# ATMEGA2560_Board.net
KiCad netlist of a schematic drawn in EAGLE
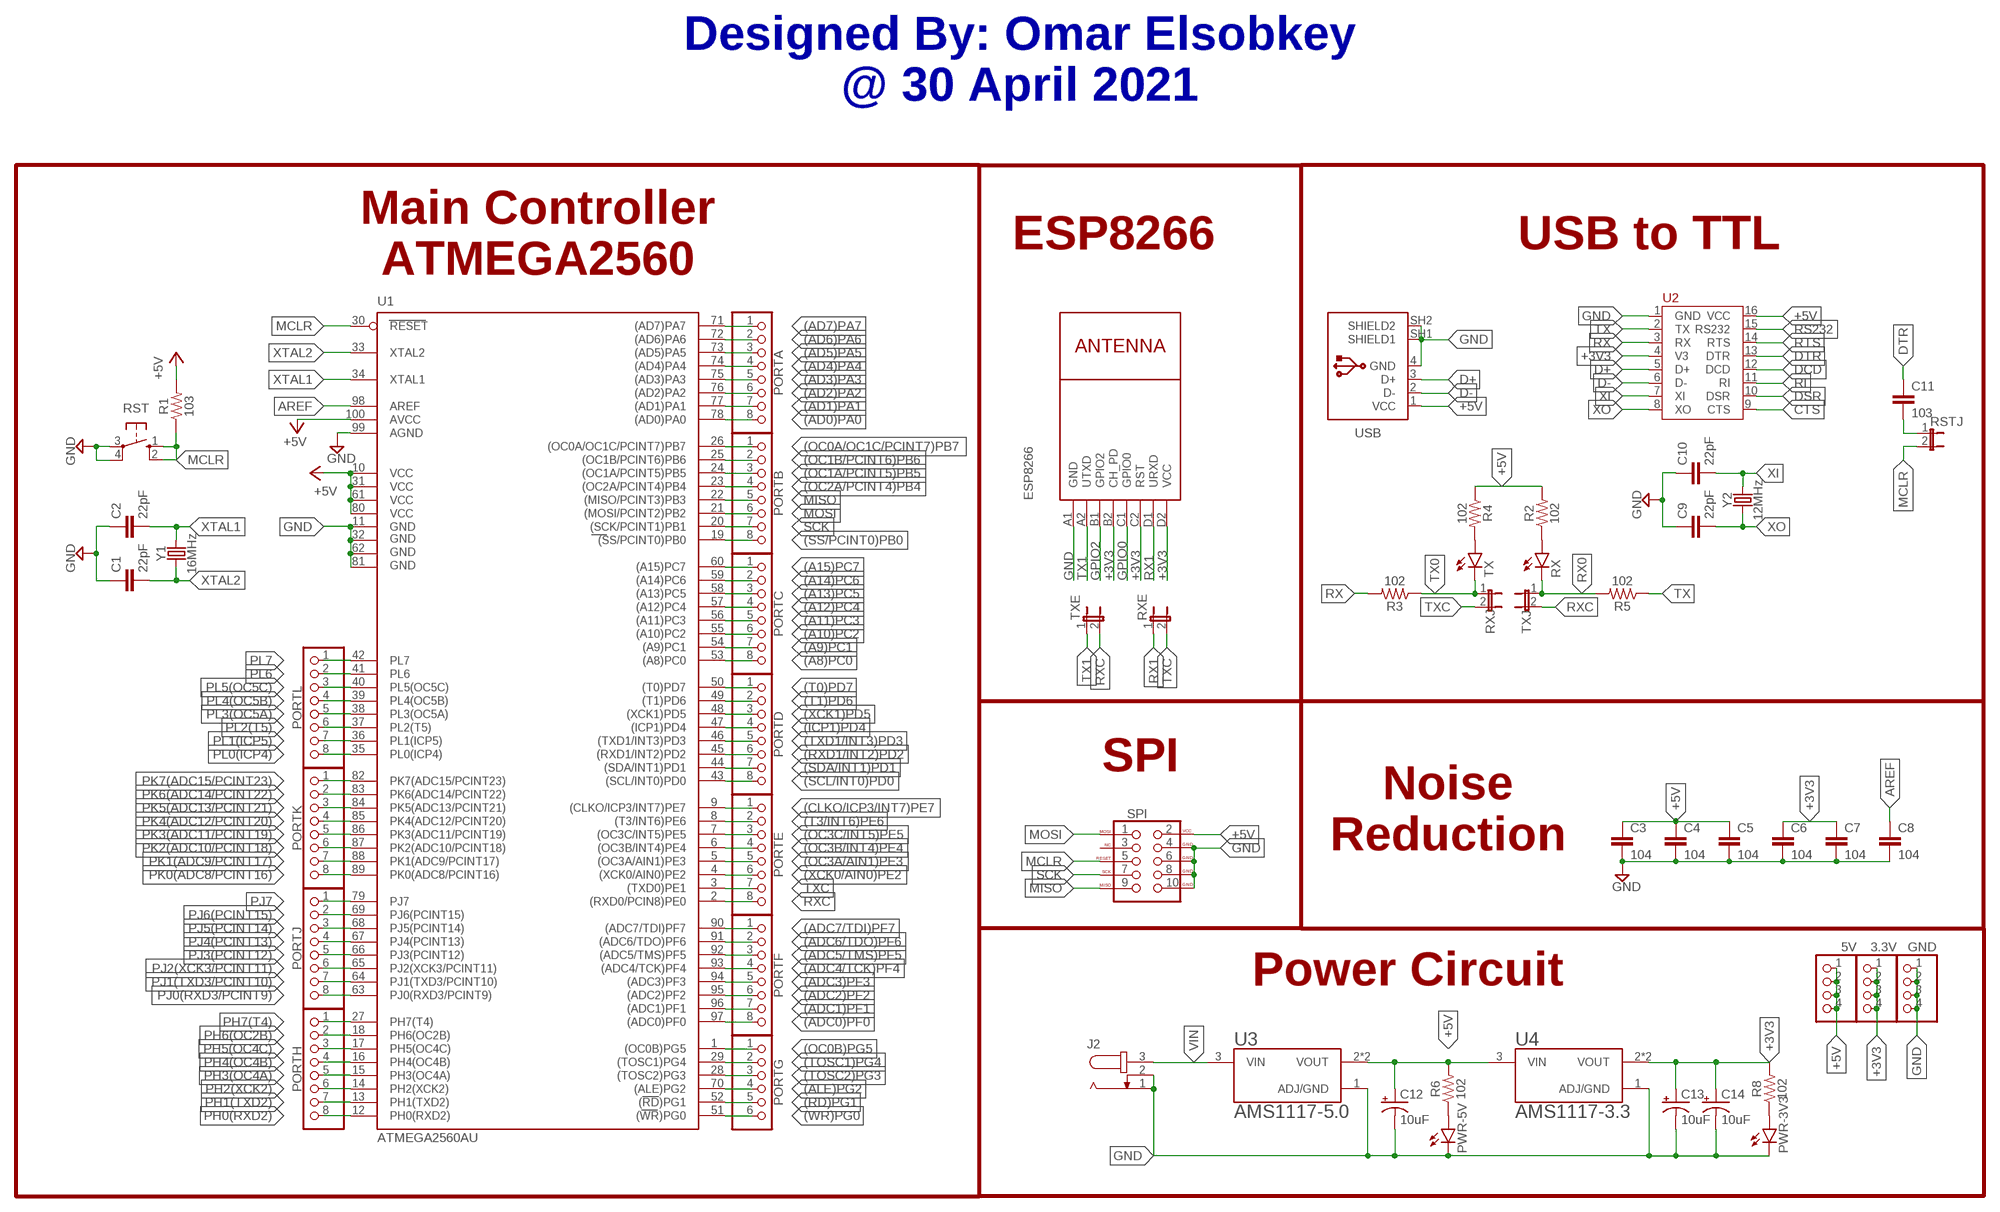
[diagram p0: schematic, sheet 1]

(export (version "E")
  (design (tool "Eeschema 10.0.6"))
  (components
    (comp (ref "3.3V")
      (value "PINHD-1X4")
      (footprint "eagle-import:1X04")
      (libsource (lib "eagle-import") (part "PINHD-1X4"))
    )
    (comp (ref "5V")
      (value "PINHD-1X4")
      (footprint "eagle-import:1X04")
      (libsource (lib "eagle-import") (part "PINHD-1X4"))
    )
    (comp (ref "C1")
      (value "22pF")
      (footprint "eagle-import:CAP-PTH-2.54")
      (libsource (lib "eagle-import") (part "22PF-PTH-2.54MM-200V-5%"))
    )
    (comp (ref "C2")
      (value "22pF")
      (footprint "eagle-import:CAP-PTH-2.54")
      (libsource (lib "eagle-import") (part "22PF-PTH-2.54MM-200V-5%"))
    )
    (comp (ref "C3")
      (value "104")
      (footprint "eagle-import:CAP-PTH-2.54")
      (libsource (lib "eagle-import") (part "22PF-PTH-2.54MM-200V-5%"))
    )
    (comp (ref "C4")
      (value "104")
      (footprint "eagle-import:CAP-PTH-2.54")
      (libsource (lib "eagle-import") (part "22PF-PTH-2.54MM-200V-5%"))
    )
    (comp (ref "C5")
      (value "104")
      (footprint "eagle-import:CAP-PTH-2.54")
      (libsource (lib "eagle-import") (part "22PF-PTH-2.54MM-200V-5%"))
    )
    (comp (ref "C6")
      (value "104")
      (footprint "eagle-import:CAP-PTH-2.54")
      (libsource (lib "eagle-import") (part "22PF-PTH-2.54MM-200V-5%"))
    )
    (comp (ref "C7")
      (value "104")
      (footprint "eagle-import:CAP-PTH-2.54")
      (libsource (lib "eagle-import") (part "22PF-PTH-2.54MM-200V-5%"))
    )
    (comp (ref "C8")
      (value "104")
      (footprint "eagle-import:CAP-PTH-2.54")
      (libsource (lib "eagle-import") (part "22PF-PTH-2.54MM-200V-5%"))
    )
    (comp (ref "C9")
      (value "22pF")
      (footprint "eagle-import:CAP-PTH-2.54")
      (libsource (lib "eagle-import") (part "22PF-PTH-2.54MM-200V-5%"))
    )
    (comp (ref "C10")
      (value "22pF")
      (footprint "eagle-import:CAP-PTH-2.54")
      (libsource (lib "eagle-import") (part "22PF-PTH-2.54MM-200V-5%"))
    )
    (comp (ref "C11")
      (value "103")
      (footprint "eagle-import:CAP-PTH-2.54")
      (libsource (lib "eagle-import") (part "22PF-PTH-2.54MM-200V-5%"))
    )
    (comp (ref "C12")
      (value "10uF")
      (footprint "eagle-import:CPOL-RADIAL-2.5MM-5MM-KIT")
      (libsource (lib "eagle-import") (part "10UF-POLAR-RADIAL-2.5MM-KIT-25V-20%"))
    )
    (comp (ref "C13")
      (value "10uF")
      (footprint "eagle-import:CPOL-RADIAL-2.5MM-5MM-KIT")
      (libsource (lib "eagle-import") (part "10UF-POLAR-RADIAL-2.5MM-KIT-25V-20%"))
    )
    (comp (ref "C14")
      (value "10uF")
      (footprint "eagle-import:CPOL-RADIAL-2.5MM-5MM-KIT")
      (libsource (lib "eagle-import") (part "10UF-POLAR-RADIAL-2.5MM-KIT-25V-20%"))
    )
    (comp (ref "ESP8266")
      (value "WIRELESS-WIFI-ESP-01")
      (footprint "eagle-import:WIRELESS-WIFI-ESP-01")
      (libsource (lib "eagle-import") (part "WIRELESS-WIFI-ESP-01"))
    )
    (comp (ref "GND")
      (value "PINHD-1X4")
      (footprint "eagle-import:1X04")
      (libsource (lib "eagle-import") (part "PINHD-1X4"))
    )
    (comp (ref "J2")
      (value "JACK-PLUG0")
      (footprint "eagle-import:SPC4077")
      (libsource (lib "eagle-import") (part "JACK-PLUG0"))
    )
    (comp (ref "PORTA")
      (value "PINHD-1X8")
      (footprint "eagle-import:1X08")
      (libsource (lib "eagle-import") (part "PINHD-1X8"))
    )
    (comp (ref "PORTB")
      (value "PINHD-1X8")
      (footprint "eagle-import:1X08")
      (libsource (lib "eagle-import") (part "PINHD-1X8"))
    )
    (comp (ref "PORTC")
      (value "PINHD-1X8")
      (footprint "eagle-import:1X08")
      (libsource (lib "eagle-import") (part "PINHD-1X8"))
    )
    (comp (ref "PORTD")
      (value "PINHD-1X8")
      (footprint "eagle-import:1X08")
      (libsource (lib "eagle-import") (part "PINHD-1X8"))
    )
    (comp (ref "PORTE")
      (value "PINHD-1X8")
      (footprint "eagle-import:1X08")
      (libsource (lib "eagle-import") (part "PINHD-1X8"))
    )
    (comp (ref "PORTF")
      (value "PINHD-1X8")
      (footprint "eagle-import:1X08")
      (libsource (lib "eagle-import") (part "PINHD-1X8"))
    )
    (comp (ref "PORTG")
      (value "PINHD-1X6")
      (footprint "eagle-import:1X06")
      (libsource (lib "eagle-import") (part "PINHD-1X6"))
    )
    (comp (ref "PORTH")
      (value "PINHD-1X8")
      (footprint "eagle-import:1X08")
      (libsource (lib "eagle-import") (part "PINHD-1X8"))
    )
    (comp (ref "PORTJ")
      (value "PINHD-1X8")
      (footprint "eagle-import:1X08")
      (libsource (lib "eagle-import") (part "PINHD-1X8"))
    )
    (comp (ref "PORTK")
      (value "PINHD-1X8")
      (footprint "eagle-import:1X08")
      (libsource (lib "eagle-import") (part "PINHD-1X8"))
    )
    (comp (ref "PORTL")
      (value "PINHD-1X8")
      (footprint "eagle-import:1X08")
      (libsource (lib "eagle-import") (part "PINHD-1X8"))
    )
    (comp (ref "PWR-3V3")
      (value "LEDCHIP-LED0805")
      (footprint "eagle-import:CHIP-LED0805")
      (libsource (lib "eagle-import") (part "LEDCHIP-LED0805"))
    )
    (comp (ref "PWR-5V")
      (value "LEDCHIP-LED0805")
      (footprint "eagle-import:CHIP-LED0805")
      (libsource (lib "eagle-import") (part "LEDCHIP-LED0805"))
    )
    (comp (ref "R1")
      (value "103")
      (footprint "eagle-import:1206")
      (libsource (lib "eagle-import") (part "RESISTOR1206"))
    )
    (comp (ref "R2")
      (value "102")
      (footprint "eagle-import:1206")
      (libsource (lib "eagle-import") (part "RESISTOR1206"))
    )
    (comp (ref "R3")
      (value "102")
      (footprint "eagle-import:1206")
      (libsource (lib "eagle-import") (part "RESISTOR1206"))
    )
    (comp (ref "R4")
      (value "102")
      (footprint "eagle-import:1206")
      (libsource (lib "eagle-import") (part "RESISTOR1206"))
    )
    (comp (ref "R5")
      (value "102")
      (footprint "eagle-import:1206")
      (libsource (lib "eagle-import") (part "RESISTOR1206"))
    )
    (comp (ref "R6")
      (value "102")
      (footprint "eagle-import:1206")
      (libsource (lib "eagle-import") (part "RESISTOR1206"))
    )
    (comp (ref "R8")
      (value "102")
      (footprint "eagle-import:1206")
      (libsource (lib "eagle-import") (part "RESISTOR1206"))
    )
    (comp (ref "RST")
      (value "10-XX")
      (footprint "eagle-import:B3F-10XX")
      (fields (field (name "MPN") "B3F-1000"))
      (libsource (lib "eagle-import") (part "10-XX"))
    )
    (comp (ref "RSTJ")
      (value "JP1E")
      (footprint "eagle-import:JP1")
      (libsource (lib "eagle-import") (part "JP1E"))
    )
    (comp (ref "RX")
      (value "LEDCHIP-LED0805")
      (footprint "eagle-import:CHIP-LED0805")
      (libsource (lib "eagle-import") (part "LEDCHIP-LED0805"))
    )
    (comp (ref "RXE")
      (value "JP1E")
      (footprint "eagle-import:JP1")
      (libsource (lib "eagle-import") (part "JP1E"))
    )
    (comp (ref "RXJ")
      (value "JP1E")
      (footprint "eagle-import:JP1")
      (libsource (lib "eagle-import") (part "JP1E"))
    )
    (comp (ref "SPI")
      (value "AVR_SPI_PROG_5X2LOCK")
      (footprint "eagle-import:2X5-SHROUDED_LOCK")
      (libsource (lib "eagle-import") (part "AVR_SPI_PROG_5X2LOCK"))
    )
    (comp (ref "TX")
      (value "LEDCHIP-LED0805")
      (footprint "eagle-import:CHIP-LED0805")
      (libsource (lib "eagle-import") (part "LEDCHIP-LED0805"))
    )
    (comp (ref "TXE")
      (value "JP1E")
      (footprint "eagle-import:JP1")
      (libsource (lib "eagle-import") (part "JP1E"))
    )
    (comp (ref "TXJ")
      (value "JP1E")
      (footprint "eagle-import:JP1")
      (libsource (lib "eagle-import") (part "JP1E"))
    )
    (comp (ref "U1")
      (value "ATMEGA2560AU")
      (footprint "eagle-import:TQFP100")
      (libsource (lib "eagle-import") (part "ATMEGA2560AU"))
    )
    (comp (ref "U2")
      (value "CH340G")
      (footprint "eagle-import:SOP-16")
      (libsource (lib "eagle-import") (part "CH340G"))
    )
    (comp (ref "U3")
      (value "AMS1117-5.0")
      (footprint "eagle-import:AMS1117-5.0")
      (fields (field (name "MF") "Advanced Monolithic Systems"))
      (libsource (lib "eagle-import") (part "AMS1117-5.0"))
    )
    (comp (ref "U4")
      (value "AMS1117-3.3")
      (footprint "eagle-import:AMS1117-5.0")
      (fields (field (name "MF") "Advanced Monolithic Systems") (field (name "MP") "AMS1117-5.0"))
      (libsource (lib "eagle-import") (part "AMS1117-5.0"))
    )
    (comp (ref "USB")
      (value "61729-1011")
      (footprint "eagle-import:61729-1011BLF")
      (fields (field (name "MANUFACTURER") "Amphenol ICC (FCI)") (field (name "MPN") "61729-1011BLF"))
      (libsource (lib "eagle-import") (part "61729-1011"))
    )
    (comp (ref "Y1")
      (value "16MHz")
      (footprint "eagle-import:HC49U")
      (libsource (lib "eagle-import") (part "CRYSTALPTH-HC49UV"))
    )
    (comp (ref "Y2")
      (value "12MHz")
      (footprint "eagle-import:HC49U")
      (libsource (lib "eagle-import") (part "CRYSTALPTH-HC49UV"))
    )
  )
  (nets
    (net (code "1") (name "(A8)PC0") (class "Default")
      (node (ref "PORTC") (pin "8") (pinfunction "8_8") (pintype "passive"))
      (node (ref "U1") (pin "53") (pinfunction "(A8)PC0_53") (pintype "bidirectional"))
    )
    (net (code "2") (name "(A9)PC1") (class "Default")
      (node (ref "PORTC") (pin "7") (pinfunction "7_7") (pintype "passive"))
      (node (ref "U1") (pin "54") (pinfunction "(A9)PC1_54") (pintype "bidirectional"))
    )
    (net (code "3") (name "(A10)PC2") (class "Default")
      (node (ref "PORTC") (pin "6") (pinfunction "6_6") (pintype "passive"))
      (node (ref "U1") (pin "55") (pinfunction "(A10)PC2_55") (pintype "bidirectional"))
    )
    (net (code "4") (name "(A11)PC3") (class "Default")
      (node (ref "PORTC") (pin "5") (pinfunction "5_5") (pintype "passive"))
      (node (ref "U1") (pin "56") (pinfunction "(A11)PC3_56") (pintype "bidirectional"))
    )
    (net (code "5") (name "(A12)PC4") (class "Default")
      (node (ref "PORTC") (pin "4") (pinfunction "4_4") (pintype "passive"))
      (node (ref "U1") (pin "57") (pinfunction "(A12)PC4_57") (pintype "bidirectional"))
    )
    (net (code "6") (name "(A13)PC5") (class "Default")
      (node (ref "PORTC") (pin "3") (pinfunction "3_3") (pintype "passive"))
      (node (ref "U1") (pin "58") (pinfunction "(A13)PC5_58") (pintype "bidirectional"))
    )
    (net (code "7") (name "(A14)PC6") (class "Default")
      (node (ref "PORTC") (pin "2") (pinfunction "2_2") (pintype "passive"))
      (node (ref "U1") (pin "59") (pinfunction "(A14)PC6_59") (pintype "bidirectional"))
    )
    (net (code "8") (name "(A15)PC7") (class "Default")
      (node (ref "PORTC") (pin "1") (pinfunction "1_1") (pintype "passive"))
      (node (ref "U1") (pin "60") (pinfunction "(A15)PC7_60") (pintype "bidirectional"))
    )
    (net (code "9") (name "(AD0)PA0") (class "Default")
      (node (ref "PORTA") (pin "8") (pinfunction "8_8") (pintype "passive"))
      (node (ref "U1") (pin "78") (pinfunction "(AD0)PA0_78") (pintype "bidirectional"))
    )
    (net (code "10") (name "(AD1)PA1") (class "Default")
      (node (ref "PORTA") (pin "7") (pinfunction "7_7") (pintype "passive"))
      (node (ref "U1") (pin "77") (pinfunction "(AD1)PA1_77") (pintype "bidirectional"))
    )
    (net (code "11") (name "(AD2)PA2") (class "Default")
      (node (ref "PORTA") (pin "6") (pinfunction "6_6") (pintype "passive"))
      (node (ref "U1") (pin "76") (pinfunction "(AD2)PA2_76") (pintype "bidirectional"))
    )
    (net (code "12") (name "(AD3)PA3") (class "Default")
      (node (ref "PORTA") (pin "5") (pinfunction "5_5") (pintype "passive"))
      (node (ref "U1") (pin "75") (pinfunction "(AD3)PA3_75") (pintype "bidirectional"))
    )
    (net (code "13") (name "(AD4)PA4") (class "Default")
      (node (ref "PORTA") (pin "4") (pinfunction "4_4") (pintype "passive"))
      (node (ref "U1") (pin "74") (pinfunction "(AD4)PA4_74") (pintype "bidirectional"))
    )
    (net (code "14") (name "(AD5)PA5") (class "Default")
      (node (ref "PORTA") (pin "3") (pinfunction "3_3") (pintype "passive"))
      (node (ref "U1") (pin "73") (pinfunction "(AD5)PA5_73") (pintype "bidirectional"))
    )
    (net (code "15") (name "(AD6)PA6") (class "Default")
      (node (ref "PORTA") (pin "2") (pinfunction "2_2") (pintype "passive"))
      (node (ref "U1") (pin "72") (pinfunction "(AD6)PA6_72") (pintype "bidirectional"))
    )
    (net (code "16") (name "(AD7)PA7") (class "Default")
      (node (ref "PORTA") (pin "1") (pinfunction "1_1") (pintype "passive"))
      (node (ref "U1") (pin "71") (pinfunction "(AD7)PA7_71") (pintype "bidirectional"))
    )
    (net (code "17") (name "(ADC0)PF0") (class "Default")
      (node (ref "PORTF") (pin "8") (pinfunction "8_8") (pintype "passive"))
      (node (ref "U1") (pin "97") (pinfunction "(ADC0)PF0_97") (pintype "bidirectional"))
    )
    (net (code "18") (name "(ADC1)PF1") (class "Default")
      (node (ref "PORTF") (pin "7") (pinfunction "7_7") (pintype "passive"))
      (node (ref "U1") (pin "96") (pinfunction "(ADC1)PF1_96") (pintype "bidirectional"))
    )
    (net (code "19") (name "(ADC2)PF2") (class "Default")
      (node (ref "PORTF") (pin "6") (pinfunction "6_6") (pintype "passive"))
      (node (ref "U1") (pin "95") (pinfunction "(ADC2)PF2_95") (pintype "bidirectional"))
    )
    (net (code "20") (name "(ADC3)PF3") (class "Default")
      (node (ref "PORTF") (pin "5") (pinfunction "5_5") (pintype "passive"))
      (node (ref "U1") (pin "94") (pinfunction "(ADC3)PF3_94") (pintype "bidirectional"))
    )
    (net (code "21") (name "(ADC4{slash}TCK)PF4") (class "Default")
      (node (ref "PORTF") (pin "4") (pinfunction "4_4") (pintype "passive"))
      (node (ref "U1") (pin "93") (pinfunction "(ADC4/TCK)PF4_93") (pintype "bidirectional"))
    )
    (net (code "22") (name "(ADC5{slash}TMS)PF5") (class "Default")
      (node (ref "PORTF") (pin "3") (pinfunction "3_3") (pintype "passive"))
      (node (ref "U1") (pin "92") (pinfunction "(ADC5/TMS)PF5_92") (pintype "bidirectional"))
    )
    (net (code "23") (name "(ADC6{slash}TDO)PF6") (class "Default")
      (node (ref "PORTF") (pin "2") (pinfunction "2_2") (pintype "passive"))
      (node (ref "U1") (pin "91") (pinfunction "(ADC6/TDO)PF6_91") (pintype "bidirectional"))
    )
    (net (code "24") (name "(ADC7{slash}TDI)PF7") (class "Default")
      (node (ref "PORTF") (pin "1") (pinfunction "1_1") (pintype "passive"))
      (node (ref "U1") (pin "90") (pinfunction "(ADC7/TDI)PF7_90") (pintype "bidirectional"))
    )
    (net (code "25") (name "(ALE)PG2") (class "Default")
      (node (ref "PORTG") (pin "4") (pinfunction "4_4") (pintype "passive"))
      (node (ref "U1") (pin "70") (pinfunction "(ALE)PG2_70") (pintype "bidirectional"))
    )
    (net (code "26") (name "(CLKO{slash}ICP3{slash}INT7)PE7") (class "Default")
      (node (ref "PORTE") (pin "1") (pinfunction "1_1") (pintype "passive"))
      (node (ref "U1") (pin "9") (pinfunction "(CLKO/ICP3/INT7)PE7_9") (pintype "bidirectional"))
    )
    (net (code "27") (name "(ICP1)PD4") (class "Default")
      (node (ref "PORTD") (pin "4") (pinfunction "4_4") (pintype "passive"))
      (node (ref "U1") (pin "47") (pinfunction "(ICP1)PD4_47") (pintype "bidirectional"))
    )
    (net (code "28") (name "(OC0A{slash}OC1C{slash}PCINT7)PB7") (class "Default")
      (node (ref "PORTB") (pin "1") (pinfunction "1_1") (pintype "passive"))
      (node (ref "U1") (pin "26") (pinfunction "(OC0A/OC1C/PCINT7)PB7_26") (pintype "bidirectional"))
    )
    (net (code "29") (name "(OC0B)PG5") (class "Default")
      (node (ref "PORTG") (pin "1") (pinfunction "1_1") (pintype "passive"))
      (node (ref "U1") (pin "1") (pinfunction "(OC0B)PG5_1") (pintype "bidirectional"))
    )
    (net (code "30") (name "(OC1A{slash}PCINT5)PB5") (class "Default")
      (node (ref "PORTB") (pin "3") (pinfunction "3_3") (pintype "passive"))
      (node (ref "U1") (pin "24") (pinfunction "(OC1A/PCINT5)PB5_24") (pintype "bidirectional"))
    )
    (net (code "31") (name "(OC1B{slash}PCINT6)PB6") (class "Default")
      (node (ref "PORTB") (pin "2") (pinfunction "2_2") (pintype "passive"))
      (node (ref "U1") (pin "25") (pinfunction "(OC1B/PCINT6)PB6_25") (pintype "bidirectional"))
    )
    (net (code "32") (name "(OC2A{slash}PCINT4)PB4") (class "Default")
      (node (ref "PORTB") (pin "4") (pinfunction "4_4") (pintype "passive"))
      (node (ref "U1") (pin "23") (pinfunction "(OC2A/PCINT4)PB4_23") (pintype "bidirectional"))
    )
    (net (code "33") (name "(OC3A{slash}AIN1)PE3") (class "Default")
      (node (ref "PORTE") (pin "5") (pinfunction "5_5") (pintype "passive"))
      (node (ref "U1") (pin "5") (pinfunction "(OC3A/AIN1)PE3_5") (pintype "bidirectional"))
    )
    (net (code "34") (name "(OC3B{slash}INT4)PE4") (class "Default")
      (node (ref "PORTE") (pin "4") (pinfunction "4_4") (pintype "passive"))
      (node (ref "U1") (pin "6") (pinfunction "(OC3B/INT4)PE4_6") (pintype "bidirectional"))
    )
    (net (code "35") (name "(OC3C{slash}INT5)PE5") (class "Default")
      (node (ref "PORTE") (pin "3") (pinfunction "3_3") (pintype "passive"))
      (node (ref "U1") (pin "7") (pinfunction "(OC3C/INT5)PE5_7") (pintype "bidirectional"))
    )
    (net (code "36") (name "(RD)PG1") (class "Default")
      (node (ref "PORTG") (pin "5") (pinfunction "5_5") (pintype "passive"))
      (node (ref "U1") (pin "52") (pinfunction "(RD)PG1_52") (pintype "bidirectional"))
    )
    (net (code "37") (name "(RXD1{slash}INT2)PD2") (class "Default")
      (node (ref "PORTD") (pin "6") (pinfunction "6_6") (pintype "passive"))
      (node (ref "U1") (pin "45") (pinfunction "(RXD1/INT2)PD2_45") (pintype "bidirectional"))
    )
    (net (code "38") (name "(SCL{slash}INT0)PD0") (class "Default")
      (node (ref "PORTD") (pin "8") (pinfunction "8_8") (pintype "passive"))
      (node (ref "U1") (pin "43") (pinfunction "(SCL/INT0)PD0_43") (pintype "bidirectional"))
    )
    (net (code "39") (name "(SDA{slash}INT1)PD1") (class "Default")
      (node (ref "PORTD") (pin "7") (pinfunction "7_7") (pintype "passive"))
      (node (ref "U1") (pin "44") (pinfunction "(SDA/INT1)PD1_44") (pintype "bidirectional"))
    )
    (net (code "40") (name "(SS{slash}PCINT0)PB0") (class "Default")
      (node (ref "PORTB") (pin "8") (pinfunction "8_8") (pintype "passive"))
      (node (ref "U1") (pin "19") (pinfunction "(SS/PCINT0)PB0_19") (pintype "bidirectional"))
    )
    (net (code "41") (name "(T0)PD7") (class "Default")
      (node (ref "PORTD") (pin "1") (pinfunction "1_1") (pintype "passive"))
      (node (ref "U1") (pin "50") (pinfunction "(T0)PD7_50") (pintype "bidirectional"))
    )
    (net (code "42") (name "(T1)PD6") (class "Default")
      (node (ref "PORTD") (pin "2") (pinfunction "2_2") (pintype "passive"))
      (node (ref "U1") (pin "49") (pinfunction "(T1)PD6_49") (pintype "bidirectional"))
    )
    (net (code "43") (name "(T3{slash}INT6)PE6") (class "Default")
      (node (ref "PORTE") (pin "2") (pinfunction "2_2") (pintype "passive"))
      (node (ref "U1") (pin "8") (pinfunction "(T3/INT6)PE6_8") (pintype "bidirectional"))
    )
    (net (code "44") (name "(TOSC1)PG4") (class "Default")
      (node (ref "PORTG") (pin "2") (pinfunction "2_2") (pintype "passive"))
      (node (ref "U1") (pin "29") (pinfunction "(TOSC1)PG4_29") (pintype "bidirectional"))
    )
    (net (code "45") (name "(TOSC2)PG3") (class "Default")
      (node (ref "PORTG") (pin "3") (pinfunction "3_3") (pintype "passive"))
      (node (ref "U1") (pin "28") (pinfunction "(TOSC2)PG3_28") (pintype "bidirectional"))
    )
    (net (code "46") (name "(TXD1{slash}INT3)PD3") (class "Default")
      (node (ref "PORTD") (pin "5") (pinfunction "5_5") (pintype "passive"))
      (node (ref "U1") (pin "46") (pinfunction "(TXD1/INT3)PD3_46") (pintype "bidirectional"))
    )
    (net (code "47") (name "(WR)PG0") (class "Default")
      (node (ref "PORTG") (pin "6") (pinfunction "6_6") (pintype "passive"))
      (node (ref "U1") (pin "51") (pinfunction "(WR)PG0_51") (pintype "bidirectional"))
    )
    (net (code "48") (name "(XCK0{slash}AIN0)PE2") (class "Default")
      (node (ref "PORTE") (pin "6") (pinfunction "6_6") (pintype "passive"))
      (node (ref "U1") (pin "4") (pinfunction "(XCK0/AIN0)PE2_4") (pintype "bidirectional"))
    )
    (net (code "49") (name "(XCK1)PD5") (class "Default")
      (node (ref "PORTD") (pin "3") (pinfunction "3_3") (pintype "passive"))
      (node (ref "U1") (pin "48") (pinfunction "(XCK1)PD5_48") (pintype "bidirectional"))
    )
    (net (code "50") (name "+3V3") (class "Default")
      (node (ref "3.3V") (pin "1") (pinfunction "1_1") (pintype "passive"))
      (node (ref "3.3V") (pin "2") (pinfunction "2_2") (pintype "passive"))
      (node (ref "3.3V") (pin "3") (pinfunction "3_3") (pintype "passive"))
      (node (ref "3.3V") (pin "4") (pinfunction "4_4") (pintype "passive"))
      (node (ref "C13") (pin "1") (pinfunction "+_1") (pintype "passive"))
      (node (ref "C14") (pin "1") (pinfunction "+_1") (pintype "passive"))
      (node (ref "C6") (pin "1") (pinfunction "1_1") (pintype "passive"))
      (node (ref "C7") (pin "1") (pinfunction "1_1") (pintype "passive"))
      (node (ref "ESP8266") (pin "B2") (pinfunction "CH_PD_B2") (pintype "bidirectional"))
      (node (ref "ESP8266") (pin "C2") (pinfunction "RST_C2") (pintype "bidirectional"))
      (node (ref "ESP8266") (pin "D2") (pinfunction "VCC_D2") (pintype "power_in"))
      (node (ref "R8") (pin "2") (pinfunction "2_2") (pintype "passive"))
      (node (ref "U2") (pin "4") (pinfunction "V3_4") (pintype "bidirectional"))
      (node (ref "U4") (pin "2") (pinfunction "VOUT_2") (pintype "output"))
      (node (ref "U4") (pin "4") (pinfunction "VOUT_4") (pintype "output"))
    )
    (net (code "51") (name "+5V") (class "Default")
      (node (ref "5V") (pin "1") (pinfunction "1_1") (pintype "passive"))
      (node (ref "5V") (pin "2") (pinfunction "2_2") (pintype "passive"))
      (node (ref "5V") (pin "3") (pinfunction "3_3") (pintype "passive"))
      (node (ref "5V") (pin "4") (pinfunction "4_4") (pintype "passive"))
      (node (ref "C12") (pin "1") (pinfunction "+_1") (pintype "passive"))
      (node (ref "C3") (pin "1") (pinfunction "1_1") (pintype "passive"))
      (node (ref "C4") (pin "1") (pinfunction "1_1") (pintype "passive"))
      (node (ref "C5") (pin "1") (pinfunction "1_1") (pintype "passive"))
      (node (ref "R1") (pin "2") (pinfunction "2_2") (pintype "passive"))
      (node (ref "R2") (pin "2") (pinfunction "2_2") (pintype "passive"))
      (node (ref "R4") (pin "1") (pinfunction "1_1") (pintype "passive"))
      (node (ref "R6") (pin "2") (pinfunction "2_2") (pintype "passive"))
      (node (ref "SPI") (pin "2") (pinfunction "VCC_2") (pintype "power_in"))
      (node (ref "U1") (pin "10") (pinfunction "VCC_10") (pintype "power_in"))
      (node (ref "U1") (pin "100") (pinfunction "AVCC_100") (pintype "power_in"))
      (node (ref "U1") (pin "31") (pinfunction "VCC1_31") (pintype "power_in"))
      (node (ref "U1") (pin "61") (pinfunction "VCC2_61") (pintype "power_in"))
      (node (ref "U1") (pin "80") (pinfunction "VCC3_80") (pintype "power_in"))
      (node (ref "U2") (pin "16") (pinfunction "VCC_16") (pintype "bidirectional"))
      (node (ref "U3") (pin "2") (pinfunction "VOUT_2") (pintype "output"))
      (node (ref "U3") (pin "4") (pinfunction "VOUT_4") (pintype "output"))
      (node (ref "U4") (pin "3") (pinfunction "VIN_3") (pintype "input"))
      (node (ref "USB") (pin "1") (pinfunction "VCC_1") (pintype "power_in"))
    )
    (net (code "52") (name "/GPIO0") (class "Default")
      (node (ref "ESP8266") (pin "C1") (pinfunction "GPIO0_C1") (pintype "bidirectional"))
    )
    (net (code "53") (name "/GPIO2") (class "Default")
      (node (ref "ESP8266") (pin "B1") (pinfunction "GPIO2_B1") (pintype "bidirectional"))
    )
    (net (code "54") (name "AREF") (class "Default")
      (node (ref "C8") (pin "1") (pinfunction "1_1") (pintype "passive"))
      (node (ref "U1") (pin "98") (pinfunction "AREF_98") (pintype "bidirectional"))
    )
    (net (code "55") (name "CTS") (class "Default")
      (node (ref "U2") (pin "9") (pinfunction "CTS_9") (pintype "bidirectional"))
    )
    (net (code "56") (name "D+") (class "Default")
      (node (ref "U2") (pin "5") (pinfunction "D+_5") (pintype "bidirectional"))
      (node (ref "USB") (pin "3") (pinfunction "D+_3") (pintype "bidirectional"))
    )
    (net (code "57") (name "D-") (class "Default")
      (node (ref "U2") (pin "6") (pinfunction "D-_6") (pintype "bidirectional"))
      (node (ref "USB") (pin "2") (pinfunction "D-_2") (pintype "bidirectional"))
    )
    (net (code "58") (name "DCD") (class "Default")
      (node (ref "U2") (pin "12") (pinfunction "DCD_12") (pintype "bidirectional"))
    )
    (net (code "59") (name "DSR") (class "Default")
      (node (ref "U2") (pin "10") (pinfunction "DSR_10") (pintype "bidirectional"))
    )
    (net (code "60") (name "DTR") (class "Default")
      (node (ref "C11") (pin "1") (pinfunction "1_1") (pintype "passive"))
      (node (ref "U2") (pin "13") (pinfunction "DTR_13") (pintype "bidirectional"))
    )
    (net (code "61") (name "GND") (class "Default")
      (node (ref "C1") (pin "1") (pinfunction "1_1") (pintype "passive"))
      (node (ref "C10") (pin "1") (pinfunction "1_1") (pintype "passive"))
      (node (ref "C12") (pin "2") (pinfunction "-_2") (pintype "passive"))
      (node (ref "C13") (pin "2") (pinfunction "-_2") (pintype "passive"))
      (node (ref "C14") (pin "2") (pinfunction "-_2") (pintype "passive"))
      (node (ref "C2") (pin "1") (pinfunction "1_1") (pintype "passive"))
      (node (ref "C3") (pin "2") (pinfunction "2_2") (pintype "passive"))
      (node (ref "C4") (pin "2") (pinfunction "2_2") (pintype "passive"))
      (node (ref "C5") (pin "2") (pinfunction "2_2") (pintype "passive"))
      (node (ref "C6") (pin "2") (pinfunction "2_2") (pintype "passive"))
      (node (ref "C7") (pin "2") (pinfunction "2_2") (pintype "passive"))
      (node (ref "C8") (pin "2") (pinfunction "2_2") (pintype "passive"))
      (node (ref "C9") (pin "1") (pinfunction "1_1") (pintype "passive"))
      (node (ref "ESP8266") (pin "A1") (pinfunction "GND_A1") (pintype "power_in"))
      (node (ref "GND") (pin "1") (pinfunction "1_1") (pintype "passive"))
      (node (ref "GND") (pin "2") (pinfunction "2_2") (pintype "passive"))
      (node (ref "GND") (pin "3") (pinfunction "3_3") (pintype "passive"))
      (node (ref "GND") (pin "4") (pinfunction "4_4") (pintype "passive"))
      (node (ref "J2") (pin "1") (pinfunction "1_1") (pintype "passive"))
      (node (ref "J2") (pin "2") (pinfunction "2_2") (pintype "passive"))
      (node (ref "PWR-3V3") (pin "C") (pinfunction "C_C") (pintype "passive"))
      (node (ref "PWR-5V") (pin "C") (pinfunction "C_C") (pintype "passive"))
      (node (ref "RST") (pin "3") (pinfunction "P_3") (pintype "passive"))
      (node (ref "RST") (pin "4") (pinfunction "P1_4") (pintype "passive"))
      (node (ref "SPI") (pin "10") (pinfunction "GND_10") (pintype "power_in"))
      (node (ref "SPI") (pin "4") (pinfunction "GND_4") (pintype "power_in"))
      (node (ref "SPI") (pin "6") (pinfunction "GND_6") (pintype "power_in"))
      (node (ref "SPI") (pin "8") (pinfunction "GND_8") (pintype "power_in"))
      (node (ref "U1") (pin "11") (pinfunction "GND_11") (pintype "power_in"))
      (node (ref "U1") (pin "32") (pinfunction "GND1_32") (pintype "power_in"))
      (node (ref "U1") (pin "62") (pinfunction "GND2_62") (pintype "power_in"))
      (node (ref "U1") (pin "81") (pinfunction "GND3_81") (pintype "power_in"))
      (node (ref "U1") (pin "99") (pinfunction "AGND_99") (pintype "power_in"))
      (node (ref "U2") (pin "1") (pinfunction "GND_1") (pintype "bidirectional"))
      (node (ref "U3") (pin "1") (pinfunction "ADJ/GND_1") (pintype "power_in"))
      (node (ref "U4") (pin "1") (pinfunction "ADJ/GND_1") (pintype "power_in"))
      (node (ref "USB") (pin "4") (pinfunction "GND_4") (pintype "power_in"))
      (node (ref "USB") (pin "SH1") (pinfunction "SHIELD1_SH1") (pintype "power_in"))
      (node (ref "USB") (pin "SH2") (pinfunction "SHIELD2_SH2") (pintype "power_in"))
    )
    (net (code "62") (name "MCLR") (class "Default")
      (node (ref "R1") (pin "1") (pinfunction "1_1") (pintype "passive"))
      (node (ref "RST") (pin "1") (pinfunction "S_1") (pintype "passive"))
      (node (ref "RST") (pin "2") (pinfunction "S1_2") (pintype "passive"))
      (node (ref "RSTJ") (pin "2") (pinfunction "2_2") (pintype "passive"))
      (node (ref "SPI") (pin "5") (pinfunction "RESET_5") (pintype "passive"))
      (node (ref "U1") (pin "30") (pinfunction "RESET_30") (pintype "input"))
    )
    (net (code "63") (name "MISO") (class "Default")
      (node (ref "PORTB") (pin "5") (pinfunction "5_5") (pintype "passive"))
      (node (ref "SPI") (pin "9") (pinfunction "MISO_9") (pintype "passive"))
      (node (ref "U1") (pin "22") (pinfunction "(MISO/PCINT3)PB3_22") (pintype "bidirectional"))
    )
    (net (code "64") (name "MOSI") (class "Default")
      (node (ref "PORTB") (pin "6") (pinfunction "6_6") (pintype "passive"))
      (node (ref "SPI") (pin "1") (pinfunction "MOSI_1") (pintype "passive"))
      (node (ref "U1") (pin "21") (pinfunction "(MOSI/PCINT2)PB2_21") (pintype "bidirectional"))
    )
    (net (code "65") (name "Net-(C11-Pad2)") (class "Default")
      (node (ref "C11") (pin "2") (pinfunction "2_2") (pintype "passive"))
      (node (ref "RSTJ") (pin "1") (pinfunction "1_1") (pintype "passive"))
    )
    (net (code "66") (name "Net-(PWR-3V3-PadA)") (class "Default")
      (node (ref "PWR-3V3") (pin "A") (pinfunction "A_A") (pintype "passive"))
      (node (ref "R8") (pin "1") (pinfunction "1_1") (pintype "passive"))
    )
    (net (code "67") (name "Net-(PWR-5V-PadA)") (class "Default")
      (node (ref "PWR-5V") (pin "A") (pinfunction "A_A") (pintype "passive"))
      (node (ref "R6") (pin "1") (pinfunction "1_1") (pintype "passive"))
    )
    (net (code "68") (name "Net-(R2-Pad1)") (class "Default")
      (node (ref "R2") (pin "1") (pinfunction "1_1") (pintype "passive"))
      (node (ref "RX") (pin "A") (pinfunction "A_A") (pintype "passive"))
    )
    (net (code "69") (name "Net-(R4-Pad2)") (class "Default")
      (node (ref "R4") (pin "2") (pinfunction "2_2") (pintype "passive"))
      (node (ref "TX") (pin "A") (pinfunction "A_A") (pintype "passive"))
    )
    (net (code "70") (name "PH0(RXD2)") (class "Default")
      (node (ref "PORTH") (pin "8") (pinfunction "8_8") (pintype "passive"))
      (node (ref "U1") (pin "12") (pinfunction "PH0(RXD2)_12") (pintype "bidirectional"))
    )
    (net (code "71") (name "PH1(TXD2)") (class "Default")
      (node (ref "PORTH") (pin "7") (pinfunction "7_7") (pintype "passive"))
      (node (ref "U1") (pin "13") (pinfunction "PH1(TXD2)_13") (pintype "bidirectional"))
    )
    (net (code "72") (name "PH2(XCK2)") (class "Default")
      (node (ref "PORTH") (pin "6") (pinfunction "6_6") (pintype "passive"))
      (node (ref "U1") (pin "14") (pinfunction "PH2(XCK2)_14") (pintype "bidirectional"))
    )
    (net (code "73") (name "PH3(OC4A)") (class "Default")
      (node (ref "PORTH") (pin "5") (pinfunction "5_5") (pintype "passive"))
      (node (ref "U1") (pin "15") (pinfunction "PH3(OC4A)_15") (pintype "bidirectional"))
    )
    (net (code "74") (name "PH4(OC4B)") (class "Default")
      (node (ref "PORTH") (pin "4") (pinfunction "4_4") (pintype "passive"))
      (node (ref "U1") (pin "16") (pinfunction "PH4(OC4B)_16") (pintype "bidirectional"))
    )
    (net (code "75") (name "PH5(OC4C)") (class "Default")
      (node (ref "PORTH") (pin "3") (pinfunction "3_3") (pintype "passive"))
      (node (ref "U1") (pin "17") (pinfunction "PH5(OC4C)_17") (pintype "bidirectional"))
    )
    (net (code "76") (name "PH6(OC2B)") (class "Default")
      (node (ref "PORTH") (pin "2") (pinfunction "2_2") (pintype "passive"))
      (node (ref "U1") (pin "18") (pinfunction "PH6(OC2B)_18") (pintype "bidirectional"))
    )
    (net (code "77") (name "PH7(T4)") (class "Default")
      (node (ref "PORTH") (pin "1") (pinfunction "1_1") (pintype "passive"))
      (node (ref "U1") (pin "27") (pinfunction "PH7(T4)_27") (pintype "bidirectional"))
    )
    (net (code "78") (name "PJ0(RXD3{slash}PCINT9)") (class "Default")
      (node (ref "PORTJ") (pin "8") (pinfunction "8_8") (pintype "passive"))
      (node (ref "U1") (pin "63") (pinfunction "PJ0(RXD3/PCINT9)_63") (pintype "bidirectional"))
    )
    (net (code "79") (name "PJ1(TXD3{slash}PCINT10)") (class "Default")
      (node (ref "PORTJ") (pin "7") (pinfunction "7_7") (pintype "passive"))
      (node (ref "U1") (pin "64") (pinfunction "PJ1(TXD3/PCINT10)_64") (pintype "bidirectional"))
    )
    (net (code "80") (name "PJ2(XCK3{slash}PCINT11)") (class "Default")
      (node (ref "PORTJ") (pin "6") (pinfunction "6_6") (pintype "passive"))
      (node (ref "U1") (pin "65") (pinfunction "PJ2(XCK3/PCINT11)_65") (pintype "bidirectional"))
    )
    (net (code "81") (name "PJ3(PCINT12)") (class "Default")
      (node (ref "PORTJ") (pin "5") (pinfunction "5_5") (pintype "passive"))
      (node (ref "U1") (pin "66") (pinfunction "PJ3(PCINT12)_66") (pintype "bidirectional"))
    )
    (net (code "82") (name "PJ4(PCINT13)") (class "Default")
      (node (ref "PORTJ") (pin "4") (pinfunction "4_4") (pintype "passive"))
      (node (ref "U1") (pin "67") (pinfunction "PJ4(PCINT13)_67") (pintype "bidirectional"))
    )
    (net (code "83") (name "PJ5(PCINT14)") (class "Default")
      (node (ref "PORTJ") (pin "3") (pinfunction "3_3") (pintype "passive"))
      (node (ref "U1") (pin "68") (pinfunction "PJ5(PCINT14)_68") (pintype "bidirectional"))
    )
    (net (code "84") (name "PJ6(PCINT15)") (class "Default")
      (node (ref "PORTJ") (pin "2") (pinfunction "2_2") (pintype "passive"))
      (node (ref "U1") (pin "69") (pinfunction "PJ6(PCINT15)_69") (pintype "bidirectional"))
    )
    (net (code "85") (name "PJ7") (class "Default")
      (node (ref "PORTJ") (pin "1") (pinfunction "1_1") (pintype "passive"))
      (node (ref "U1") (pin "79") (pinfunction "PJ7_79") (pintype "bidirectional"))
    )
    (net (code "86") (name "PK0(ADC8{slash}PCINT16)") (class "Default")
      (node (ref "PORTK") (pin "8") (pinfunction "8_8") (pintype "passive"))
      (node (ref "U1") (pin "89") (pinfunction "PK0(ADC8/PCINT16)_89") (pintype "bidirectional"))
    )
    (net (code "87") (name "PK1(ADC9{slash}PCINT17)") (class "Default")
      (node (ref "PORTK") (pin "7") (pinfunction "7_7") (pintype "passive"))
      (node (ref "U1") (pin "88") (pinfunction "PK1(ADC9/PCINT17)_88") (pintype "bidirectional"))
    )
    (net (code "88") (name "PK2(ADC10{slash}PCINT18)") (class "Default")
      (node (ref "PORTK") (pin "6") (pinfunction "6_6") (pintype "passive"))
      (node (ref "U1") (pin "87") (pinfunction "PK2(ADC10/PCINT18)_87") (pintype "bidirectional"))
    )
    (net (code "89") (name "PK3(ADC11{slash}PCINT19)") (class "Default")
      (node (ref "PORTK") (pin "5") (pinfunction "5_5") (pintype "passive"))
      (node (ref "U1") (pin "86") (pinfunction "PK3(ADC11/PCINT19)_86") (pintype "bidirectional"))
    )
    (net (code "90") (name "PK4(ADC12{slash}PCINT20)") (class "Default")
      (node (ref "PORTK") (pin "4") (pinfunction "4_4") (pintype "passive"))
      (node (ref "U1") (pin "85") (pinfunction "PK4(ADC12/PCINT20)_85") (pintype "bidirectional"))
    )
    (net (code "91") (name "PK5(ADC13{slash}PCINT21)") (class "Default")
      (node (ref "PORTK") (pin "3") (pinfunction "3_3") (pintype "passive"))
      (node (ref "U1") (pin "84") (pinfunction "PK5(ADC13/PCINT21)_84") (pintype "bidirectional"))
    )
    (net (code "92") (name "PK6(ADC14{slash}PCINT22)") (class "Default")
      (node (ref "PORTK") (pin "2") (pinfunction "2_2") (pintype "passive"))
      (node (ref "U1") (pin "83") (pinfunction "PK6(ADC14/PCINT22)_83") (pintype "bidirectional"))
    )
    (net (code "93") (name "PK7(ADC15{slash}PCINT23)") (class "Default")
      (node (ref "PORTK") (pin "1") (pinfunction "1_1") (pintype "passive"))
      (node (ref "U1") (pin "82") (pinfunction "PK7(ADC15/PCINT23)_82") (pintype "bidirectional"))
    )
    (net (code "94") (name "PL0(ICP4)") (class "Default")
      (node (ref "PORTL") (pin "8") (pinfunction "8_8") (pintype "passive"))
      (node (ref "U1") (pin "35") (pinfunction "PL0(ICP4)_35") (pintype "bidirectional"))
    )
    (net (code "95") (name "PL1(ICP5)") (class "Default")
      (node (ref "PORTL") (pin "7") (pinfunction "7_7") (pintype "passive"))
      (node (ref "U1") (pin "36") (pinfunction "PL1(ICP5)_36") (pintype "bidirectional"))
    )
    (net (code "96") (name "PL2(T5)") (class "Default")
      (node (ref "PORTL") (pin "6") (pinfunction "6_6") (pintype "passive"))
      (node (ref "U1") (pin "37") (pinfunction "PL2(T5)_37") (pintype "bidirectional"))
    )
    (net (code "97") (name "PL3(OC5A)") (class "Default")
      (node (ref "PORTL") (pin "5") (pinfunction "5_5") (pintype "passive"))
      (node (ref "U1") (pin "38") (pinfunction "PL3(OC5A)_38") (pintype "bidirectional"))
    )
    (net (code "98") (name "PL4(OC5B)") (class "Default")
      (node (ref "PORTL") (pin "4") (pinfunction "4_4") (pintype "passive"))
      (node (ref "U1") (pin "39") (pinfunction "PL4(OC5B)_39") (pintype "bidirectional"))
    )
    (net (code "99") (name "PL5(OC5C)") (class "Default")
      (node (ref "PORTL") (pin "3") (pinfunction "3_3") (pintype "passive"))
      (node (ref "U1") (pin "40") (pinfunction "PL5(OC5C)_40") (pintype "bidirectional"))
    )
    (net (code "100") (name "PL6") (class "Default")
      (node (ref "PORTL") (pin "2") (pinfunction "2_2") (pintype "passive"))
      (node (ref "U1") (pin "41") (pinfunction "PL6_41") (pintype "bidirectional"))
    )
    (net (code "101") (name "PL7") (class "Default")
      (node (ref "PORTL") (pin "1") (pinfunction "1_1") (pintype "passive"))
      (node (ref "U1") (pin "42") (pinfunction "PL7_42") (pintype "bidirectional"))
    )
    (net (code "102") (name "RI") (class "Default")
      (node (ref "U2") (pin "11") (pinfunction "RI_11") (pintype "bidirectional"))
    )
    (net (code "103") (name "RS232") (class "Default")
      (node (ref "U2") (pin "15") (pinfunction "RS232_15") (pintype "bidirectional"))
    )
    (net (code "104") (name "RTS") (class "Default")
      (node (ref "U2") (pin "14") (pinfunction "RTS_14") (pintype "bidirectional"))
    )
    (net (code "105") (name "RX") (class "Default")
      (node (ref "R3") (pin "2") (pinfunction "2_2") (pintype "passive"))
      (node (ref "U2") (pin "3") (pinfunction "RX_3") (pintype "bidirectional"))
    )
    (net (code "106") (name "RX0") (class "Default")
      (node (ref "R5") (pin "2") (pinfunction "2_2") (pintype "passive"))
      (node (ref "RX") (pin "C") (pinfunction "C_C") (pintype "passive"))
      (node (ref "TXJ") (pin "1") (pinfunction "1_1") (pintype "passive"))
    )
    (net (code "107") (name "RX1") (class "Default")
      (node (ref "ESP8266") (pin "D1") (pinfunction "URXD_D1") (pintype "bidirectional"))
      (node (ref "RXE") (pin "1") (pinfunction "1_1") (pintype "passive"))
    )
    (net (code "108") (name "RXC") (class "Default")
      (node (ref "PORTE") (pin "8") (pinfunction "8_8") (pintype "passive"))
      (node (ref "TXE") (pin "2") (pinfunction "2_2") (pintype "passive"))
      (node (ref "TXJ") (pin "2") (pinfunction "2_2") (pintype "passive"))
      (node (ref "U1") (pin "2") (pinfunction "(RXD0/PCIN8)PE0_2") (pintype "bidirectional"))
    )
    (net (code "109") (name "SCK") (class "Default")
      (node (ref "PORTB") (pin "7") (pinfunction "7_7") (pintype "passive"))
      (node (ref "SPI") (pin "7") (pinfunction "SCK_7") (pintype "passive"))
      (node (ref "U1") (pin "20") (pinfunction "(SCK/PCINT1)PB1_20") (pintype "bidirectional"))
    )
    (net (code "110") (name "TX") (class "Default")
      (node (ref "R5") (pin "1") (pinfunction "1_1") (pintype "passive"))
      (node (ref "U2") (pin "2") (pinfunction "TX_2") (pintype "bidirectional"))
    )
    (net (code "111") (name "TX0") (class "Default")
      (node (ref "R3") (pin "1") (pinfunction "1_1") (pintype "passive"))
      (node (ref "RXJ") (pin "1") (pinfunction "1_1") (pintype "passive"))
      (node (ref "TX") (pin "C") (pinfunction "C_C") (pintype "passive"))
    )
    (net (code "112") (name "TX1") (class "Default")
      (node (ref "ESP8266") (pin "A2") (pinfunction "UTXD_A2") (pintype "bidirectional"))
      (node (ref "TXE") (pin "1") (pinfunction "1_1") (pintype "passive"))
    )
    (net (code "113") (name "TXC") (class "Default")
      (node (ref "PORTE") (pin "7") (pinfunction "7_7") (pintype "passive"))
      (node (ref "RXE") (pin "2") (pinfunction "2_2") (pintype "passive"))
      (node (ref "RXJ") (pin "2") (pinfunction "2_2") (pintype "passive"))
      (node (ref "U1") (pin "3") (pinfunction "(TXD0)PE1_3") (pintype "bidirectional"))
    )
    (net (code "114") (name "VIN") (class "Default")
      (node (ref "J2") (pin "3") (pinfunction "3_3") (pintype "passive"))
      (node (ref "U3") (pin "3") (pinfunction "VIN_3") (pintype "input"))
    )
    (net (code "115") (name "XI") (class "Default")
      (node (ref "C10") (pin "2") (pinfunction "2_2") (pintype "passive"))
      (node (ref "U2") (pin "7") (pinfunction "XI_7") (pintype "bidirectional"))
      (node (ref "Y2") (pin "2") (pinfunction "2_2") (pintype "passive"))
    )
    (net (code "116") (name "XO") (class "Default")
      (node (ref "C9") (pin "2") (pinfunction "2_2") (pintype "passive"))
      (node (ref "U2") (pin "8") (pinfunction "XO_8") (pintype "bidirectional"))
      (node (ref "Y2") (pin "1") (pinfunction "1_1") (pintype "passive"))
    )
    (net (code "117") (name "XTAL1") (class "Default")
      (node (ref "C2") (pin "2") (pinfunction "2_2") (pintype "passive"))
      (node (ref "U1") (pin "34") (pinfunction "XTAL1_34") (pintype "input"))
      (node (ref "Y1") (pin "2") (pinfunction "2_2") (pintype "passive"))
    )
    (net (code "118") (name "XTAL2") (class "Default")
      (node (ref "C1") (pin "2") (pinfunction "2_2") (pintype "passive"))
      (node (ref "U1") (pin "33") (pinfunction "XTAL2_33") (pintype "output"))
      (node (ref "Y1") (pin "1") (pinfunction "1_1") (pintype "passive"))
    )
    (net (code "119") (name "unconnected-(SPI-NC-Pad3)") (class "Default")
      (node (ref "SPI") (pin "3") (pinfunction "NC_3") (pintype "no_connect"))
    )
  )
)
